# Pro_Trinket_Keyboard_V3_3.net
KiCad netlist of a schematic drawn in EAGLE
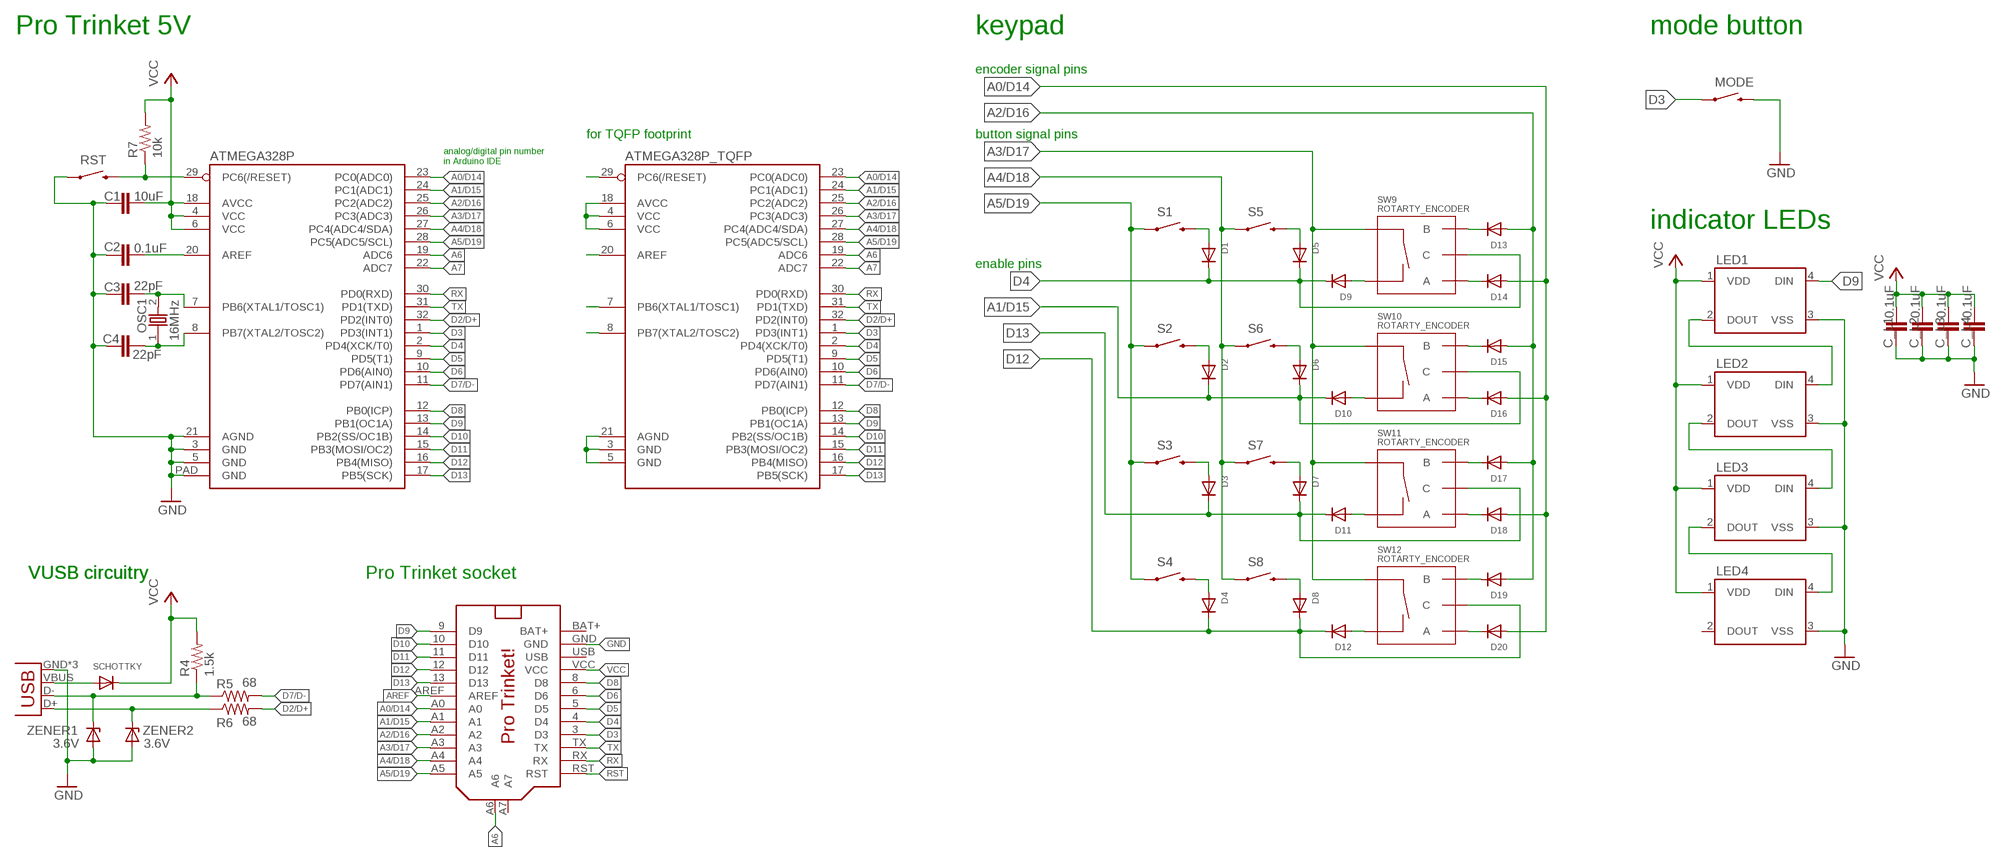
[diagram p0: schematic, sheet 1]

(export (version "E")
  (design (tool "Eeschema 10.0.6"))
  (components
    (comp (ref "ATMEGA328P")
      (value "ATMEGA328P_MLFMLF32")
      (footprint "eagle-import:MLF32-PAD")
      (libsource (lib "eagle-import") (part "ATMEGA328P_MLFMLF32"))
    )
    (comp (ref "ATMEGA328P_TQFP")
      (value "ATMEGA328P_TQFP")
      (footprint "eagle-import:TQFP32-08")
      (libsource (lib "eagle-import") (part "ATMEGA328P_TQFP"))
    )
    (comp (ref "C1")
      (value "10uF")
      (footprint "eagle-import:0603-CAP")
      (libsource (lib "eagle-import") (part "10UF-6.3V-20%(0603)"))
    )
    (comp (ref "C2")
      (value "0.1uF")
      (footprint "eagle-import:0603-CAP")
      (libsource (lib "eagle-import") (part "22PF-50V-5%(0603)"))
    )
    (comp (ref "C3")
      (value "22pF")
      (footprint "eagle-import:0603-CAP")
      (libsource (lib "eagle-import") (part "22PF-50V-5%(0603)"))
    )
    (comp (ref "C4")
      (value "22pF")
      (footprint "eagle-import:0603-CAP")
      (libsource (lib "eagle-import") (part "22PF-50V-5%(0603)"))
    )
    (comp (ref "C_L1")
      (value "0.1uF")
      (footprint "eagle-import:0603-CAP")
      (libsource (lib "eagle-import") (part "22PF-50V-5%(0603)"))
    )
    (comp (ref "C_L2")
      (value "0.1uF")
      (footprint "eagle-import:0603-CAP")
      (libsource (lib "eagle-import") (part "22PF-50V-5%(0603)"))
    )
    (comp (ref "C_L3")
      (value "0.1uF")
      (footprint "eagle-import:0603-CAP")
      (libsource (lib "eagle-import") (part "22PF-50V-5%(0603)"))
    )
    (comp (ref "C_L4")
      (value "0.1uF")
      (footprint "eagle-import:0603-CAP")
      (libsource (lib "eagle-import") (part "22PF-50V-5%(0603)"))
    )
    (comp (ref "D1")
      (value "DIODESOD-123")
      (footprint "eagle-import:SOD-123")
      (libsource (lib "eagle-import") (part "DIODESOD-123"))
    )
    (comp (ref "D2")
      (value "DIODESOD-123")
      (footprint "eagle-import:SOD-123")
      (libsource (lib "eagle-import") (part "DIODESOD-123"))
    )
    (comp (ref "D3")
      (value "DIODESOD-123")
      (footprint "eagle-import:SOD-123")
      (libsource (lib "eagle-import") (part "DIODESOD-123"))
    )
    (comp (ref "D4")
      (value "DIODESOD-123")
      (footprint "eagle-import:SOD-123")
      (libsource (lib "eagle-import") (part "DIODESOD-123"))
    )
    (comp (ref "D5")
      (value "DIODESOD-123")
      (footprint "eagle-import:SOD-123")
      (libsource (lib "eagle-import") (part "DIODESOD-123"))
    )
    (comp (ref "D6")
      (value "DIODESOD-123")
      (footprint "eagle-import:SOD-123")
      (libsource (lib "eagle-import") (part "DIODESOD-123"))
    )
    (comp (ref "D7")
      (value "DIODESOD-123")
      (footprint "eagle-import:SOD-123")
      (libsource (lib "eagle-import") (part "DIODESOD-123"))
    )
    (comp (ref "D8")
      (value "DIODESOD-123")
      (footprint "eagle-import:SOD-123")
      (libsource (lib "eagle-import") (part "DIODESOD-123"))
    )
    (comp (ref "D9")
      (value "DIODESOD-123")
      (footprint "eagle-import:SOD-123")
      (libsource (lib "eagle-import") (part "DIODESOD-123"))
    )
    (comp (ref "D10")
      (value "DIODESOD-123")
      (footprint "eagle-import:SOD-123")
      (libsource (lib "eagle-import") (part "DIODESOD-123"))
    )
    (comp (ref "D11")
      (value "DIODESOD-123")
      (footprint "eagle-import:SOD-123")
      (libsource (lib "eagle-import") (part "DIODESOD-123"))
    )
    (comp (ref "D12")
      (value "DIODESOD-123")
      (footprint "eagle-import:SOD-123")
      (libsource (lib "eagle-import") (part "DIODESOD-123"))
    )
    (comp (ref "D13")
      (value "DIODESOD-123")
      (footprint "eagle-import:SOD-123")
      (libsource (lib "eagle-import") (part "DIODESOD-123"))
    )
    (comp (ref "D14")
      (value "DIODESOD-123")
      (footprint "eagle-import:SOD-123")
      (libsource (lib "eagle-import") (part "DIODESOD-123"))
    )
    (comp (ref "D15")
      (value "DIODESOD-123")
      (footprint "eagle-import:SOD-123")
      (libsource (lib "eagle-import") (part "DIODESOD-123"))
    )
    (comp (ref "D16")
      (value "DIODESOD-123")
      (footprint "eagle-import:SOD-123")
      (libsource (lib "eagle-import") (part "DIODESOD-123"))
    )
    (comp (ref "D17")
      (value "DIODESOD-123")
      (footprint "eagle-import:SOD-123")
      (libsource (lib "eagle-import") (part "DIODESOD-123"))
    )
    (comp (ref "D18")
      (value "DIODESOD-123")
      (footprint "eagle-import:SOD-123")
      (libsource (lib "eagle-import") (part "DIODESOD-123"))
    )
    (comp (ref "D19")
      (value "DIODESOD-123")
      (footprint "eagle-import:SOD-123")
      (libsource (lib "eagle-import") (part "DIODESOD-123"))
    )
    (comp (ref "D20")
      (value "DIODESOD-123")
      (footprint "eagle-import:SOD-123")
      (libsource (lib "eagle-import") (part "DIODESOD-123"))
    )
    (comp (ref "JP1")
      (value "USB-MICROB")
      (footprint "eagle-import:USB-MICROB")
      (libsource (lib "eagle-import") (part "USB-MICROB"))
    )
    (comp (ref "LED1")
      (value "WS2812B")
      (footprint "eagle-import:WS2812B")
      (libsource (lib "eagle-import") (part "WS2812B"))
    )
    (comp (ref "LED2")
      (value "WS2812B")
      (footprint "eagle-import:WS2812B")
      (libsource (lib "eagle-import") (part "WS2812B"))
    )
    (comp (ref "LED3")
      (value "WS2812B")
      (footprint "eagle-import:WS2812B")
      (libsource (lib "eagle-import") (part "WS2812B"))
    )
    (comp (ref "LED4")
      (value "WS2812B")
      (footprint "eagle-import:WS2812B")
      (libsource (lib "eagle-import") (part "WS2812B"))
    )
    (comp (ref "MODE")
      (value "SWITCH-MOMENTARY-2SIDE_EZ")
      (footprint "eagle-import:TACTILE-PTH-SIDEEZ")
      (libsource (lib "eagle-import") (part "SWITCH-MOMENTARY-2SIDE_EZ"))
    )
    (comp (ref "OSC1")
      (value "16MHz")
      (footprint "eagle-import:HC-49U")
      (libsource (lib "eagle-import") (part "OSC-XTAL-HC-49U-SMD"))
    )
    (comp (ref "R4")
      (value "1.5k")
      (footprint "eagle-import:0805")
      (libsource (lib "eagle-import") (part "RESISTOR0805-RES"))
    )
    (comp (ref "R5")
      (value "68")
      (footprint "eagle-import:0805")
      (libsource (lib "eagle-import") (part "RESISTOR0805-RES"))
    )
    (comp (ref "R6")
      (value "68")
      (footprint "eagle-import:0805")
      (libsource (lib "eagle-import") (part "RESISTOR0805-RES"))
    )
    (comp (ref "R7")
      (value "10k")
      (footprint "eagle-import:0805")
      (libsource (lib "eagle-import") (part "RESISTOR0805-RES"))
    )
    (comp (ref "RST")
      (value "SWITCH-MOMENTARY-2SIDE_EZ")
      (footprint "eagle-import:TACTILE-PTH-SIDEEZ")
      (libsource (lib "eagle-import") (part "SWITCH-MOMENTARY-2SIDE_EZ"))
    )
    (comp (ref "S1")
      (value "SWITCH-MOMENTARY-212MM")
      (footprint "eagle-import:TACTILE-PTH-12MM")
      (libsource (lib "eagle-import") (part "SWITCH-MOMENTARY-212MM"))
    )
    (comp (ref "S2")
      (value "SWITCH-MOMENTARY-212MM")
      (footprint "eagle-import:TACTILE-PTH-12MM")
      (libsource (lib "eagle-import") (part "SWITCH-MOMENTARY-212MM"))
    )
    (comp (ref "S3")
      (value "SWITCH-MOMENTARY-212MM")
      (footprint "eagle-import:TACTILE-PTH-12MM")
      (libsource (lib "eagle-import") (part "SWITCH-MOMENTARY-212MM"))
    )
    (comp (ref "S4")
      (value "SWITCH-MOMENTARY-212MM")
      (footprint "eagle-import:TACTILE-PTH-12MM")
      (libsource (lib "eagle-import") (part "SWITCH-MOMENTARY-212MM"))
    )
    (comp (ref "S5")
      (value "SWITCH-MOMENTARY-212MM")
      (footprint "eagle-import:TACTILE-PTH-12MM")
      (libsource (lib "eagle-import") (part "SWITCH-MOMENTARY-212MM"))
    )
    (comp (ref "S6")
      (value "SWITCH-MOMENTARY-212MM")
      (footprint "eagle-import:TACTILE-PTH-12MM")
      (libsource (lib "eagle-import") (part "SWITCH-MOMENTARY-212MM"))
    )
    (comp (ref "S7")
      (value "SWITCH-MOMENTARY-212MM")
      (footprint "eagle-import:TACTILE-PTH-12MM")
      (libsource (lib "eagle-import") (part "SWITCH-MOMENTARY-212MM"))
    )
    (comp (ref "S8")
      (value "SWITCH-MOMENTARY-212MM")
      (footprint "eagle-import:TACTILE-PTH-12MM")
      (libsource (lib "eagle-import") (part "SWITCH-MOMENTARY-212MM"))
    )
    (comp (ref "SCHOTTKY")
      (value "DIODESMA")
      (footprint "eagle-import:SMADIODE")
      (libsource (lib "eagle-import") (part "DIODESMA"))
    )
    (comp (ref "SW9")
      (value "ROTARTY_ENCODER")
      (footprint "eagle-import:ROTARY_ENC_PLAIN")
      (libsource (lib "eagle-import") (part "ROTARTY_ENCODER"))
    )
    (comp (ref "SW10")
      (value "ROTARTY_ENCODER")
      (footprint "eagle-import:ROTARY_ENC_PLAIN")
      (libsource (lib "eagle-import") (part "ROTARTY_ENCODER"))
    )
    (comp (ref "SW11")
      (value "ROTARTY_ENCODER")
      (footprint "eagle-import:ROTARY_ENC_PLAIN")
      (libsource (lib "eagle-import") (part "ROTARTY_ENCODER"))
    )
    (comp (ref "SW12")
      (value "ROTARTY_ENCODER")
      (footprint "eagle-import:ROTARY_ENC_PLAIN")
      (libsource (lib "eagle-import") (part "ROTARTY_ENCODER"))
    )
    (comp (ref "U$2")
      (value "PRO_TRINKET")
      (footprint "eagle-import:PROTRINKET")
      (libsource (lib "eagle-import") (part "PRO_TRINKET"))
    )
    (comp (ref "ZENER1")
      (value "3.6V")
      (footprint "eagle-import:SOD80C")
      (libsource (lib "eagle-import") (part "ZENER-DIODESOD80C"))
    )
    (comp (ref "ZENER2")
      (value "3.6V")
      (footprint "eagle-import:SOD80C")
      (libsource (lib "eagle-import") (part "ZENER-DIODESOD80C"))
    )
  )
  (nets
    (net (code "1") (name "/BAT+") (class "Default")
      (node (ref "U$2") (pin "BAT+") (pinfunction "BAT+_BAT+") (pintype "power_in"))
    )
    (net (code "2") (name "/USB") (class "Default")
      (node (ref "U$2") (pin "USB") (pinfunction "USB_USB") (pintype "power_in"))
    )
    (net (code "3") (name "/XTAL1") (class "Default")
      (node (ref "ATMEGA328P") (pin "7") (pinfunction "PB6(XTAL1/TOSC1)_7") (pintype "bidirectional"))
      (node (ref "ATMEGA328P_TQFP") (pin "7") (pinfunction "PB6(XTAL1/TOSC1)_7") (pintype "bidirectional"))
      (node (ref "C3") (pin "2") (pinfunction "2_2") (pintype "passive"))
      (node (ref "OSC1") (pin "2") (pinfunction "2_2") (pintype "passive"))
    )
    (net (code "4") (name "/XTAL2") (class "Default")
      (node (ref "ATMEGA328P") (pin "8") (pinfunction "PB7(XTAL2/TOSC2)_8") (pintype "bidirectional"))
      (node (ref "ATMEGA328P_TQFP") (pin "8") (pinfunction "PB7(XTAL2/TOSC2)_8") (pintype "bidirectional"))
      (node (ref "C4") (pin "1") (pinfunction "1_1") (pintype "passive"))
      (node (ref "OSC1") (pin "1") (pinfunction "1_1") (pintype "passive"))
    )
    (net (code "5") (name "A0{slash}D14") (class "Default")
      (node (ref "ATMEGA328P") (pin "23") (pinfunction "PC0(ADC0)_23") (pintype "bidirectional"))
      (node (ref "ATMEGA328P_TQFP") (pin "23") (pinfunction "PC0(ADC0)_23") (pintype "bidirectional"))
      (node (ref "D14") (pin "A") (pinfunction "A_A") (pintype "passive"))
      (node (ref "D16") (pin "A") (pinfunction "A_A") (pintype "passive"))
      (node (ref "D18") (pin "A") (pinfunction "A_A") (pintype "passive"))
      (node (ref "D20") (pin "A") (pinfunction "A_A") (pintype "passive"))
      (node (ref "U$2") (pin "A0") (pinfunction "A0_A0") (pintype "bidirectional"))
    )
    (net (code "6") (name "A1{slash}D15") (class "Default")
      (node (ref "ATMEGA328P") (pin "24") (pinfunction "PC1(ADC1)_24") (pintype "bidirectional"))
      (node (ref "ATMEGA328P_TQFP") (pin "24") (pinfunction "PC1(ADC1)_24") (pintype "bidirectional"))
      (node (ref "D10") (pin "C") (pinfunction "C_C") (pintype "passive"))
      (node (ref "D2") (pin "C") (pinfunction "C_C") (pintype "passive"))
      (node (ref "D6") (pin "C") (pinfunction "C_C") (pintype "passive"))
      (node (ref "SW10") (pin "C") (pinfunction "C_C") (pintype "bidirectional"))
      (node (ref "U$2") (pin "A1") (pinfunction "A1_A1") (pintype "bidirectional"))
    )
    (net (code "7") (name "A2{slash}D16") (class "Default")
      (node (ref "ATMEGA328P") (pin "25") (pinfunction "PC2(ADC2)_25") (pintype "bidirectional"))
      (node (ref "ATMEGA328P_TQFP") (pin "25") (pinfunction "PC2(ADC2)_25") (pintype "bidirectional"))
      (node (ref "D13") (pin "A") (pinfunction "A_A") (pintype "passive"))
      (node (ref "D15") (pin "A") (pinfunction "A_A") (pintype "passive"))
      (node (ref "D17") (pin "A") (pinfunction "A_A") (pintype "passive"))
      (node (ref "D19") (pin "A") (pinfunction "A_A") (pintype "passive"))
      (node (ref "U$2") (pin "A2") (pinfunction "A2_A2") (pintype "bidirectional"))
    )
    (net (code "8") (name "A3{slash}D17") (class "Default")
      (node (ref "ATMEGA328P") (pin "26") (pinfunction "PC3(ADC3)_26") (pintype "bidirectional"))
      (node (ref "ATMEGA328P_TQFP") (pin "26") (pinfunction "PC3(ADC3)_26") (pintype "bidirectional"))
      (node (ref "SW10") (pin "SW+") (pinfunction "SW+_SW+") (pintype "bidirectional"))
      (node (ref "SW11") (pin "SW+") (pinfunction "SW+_SW+") (pintype "bidirectional"))
      (node (ref "SW12") (pin "SW+") (pinfunction "SW+_SW+") (pintype "bidirectional"))
      (node (ref "SW9") (pin "SW+") (pinfunction "SW+_SW+") (pintype "bidirectional"))
      (node (ref "U$2") (pin "A3") (pinfunction "A3_A3") (pintype "bidirectional"))
    )
    (net (code "9") (name "A4{slash}D18") (class "Default")
      (node (ref "ATMEGA328P") (pin "27") (pinfunction "PC4(ADC4/SDA)_27") (pintype "bidirectional"))
      (node (ref "ATMEGA328P_TQFP") (pin "27") (pinfunction "PC4(ADC4/SDA)_27") (pintype "bidirectional"))
      (node (ref "S5") (pin "1") (pinfunction "1_1") (pintype "passive"))
      (node (ref "S5") (pin "2") (pinfunction "1_2") (pintype "passive"))
      (node (ref "S6") (pin "1") (pinfunction "1_1") (pintype "passive"))
      (node (ref "S6") (pin "2") (pinfunction "1_2") (pintype "passive"))
      (node (ref "S7") (pin "1") (pinfunction "1_1") (pintype "passive"))
      (node (ref "S7") (pin "2") (pinfunction "1_2") (pintype "passive"))
      (node (ref "S8") (pin "1") (pinfunction "1_1") (pintype "passive"))
      (node (ref "S8") (pin "2") (pinfunction "1_2") (pintype "passive"))
      (node (ref "U$2") (pin "A4") (pinfunction "A4_A4") (pintype "bidirectional"))
    )
    (net (code "10") (name "A5{slash}D19") (class "Default")
      (node (ref "ATMEGA328P") (pin "28") (pinfunction "PC5(ADC5/SCL)_28") (pintype "bidirectional"))
      (node (ref "ATMEGA328P_TQFP") (pin "28") (pinfunction "PC5(ADC5/SCL)_28") (pintype "bidirectional"))
      (node (ref "S1") (pin "1") (pinfunction "1_1") (pintype "passive"))
      (node (ref "S1") (pin "2") (pinfunction "1_2") (pintype "passive"))
      (node (ref "S2") (pin "1") (pinfunction "1_1") (pintype "passive"))
      (node (ref "S2") (pin "2") (pinfunction "1_2") (pintype "passive"))
      (node (ref "S3") (pin "1") (pinfunction "1_1") (pintype "passive"))
      (node (ref "S3") (pin "2") (pinfunction "1_2") (pintype "passive"))
      (node (ref "S4") (pin "1") (pinfunction "1_1") (pintype "passive"))
      (node (ref "S4") (pin "2") (pinfunction "1_2") (pintype "passive"))
      (node (ref "U$2") (pin "A5") (pinfunction "A5_A5") (pintype "bidirectional"))
    )
    (net (code "11") (name "A6") (class "Default")
      (node (ref "ATMEGA328P") (pin "19") (pinfunction "ADC6_19") (pintype "bidirectional"))
      (node (ref "ATMEGA328P_TQFP") (pin "19") (pinfunction "ADC6_19") (pintype "bidirectional"))
      (node (ref "U$2") (pin "A6") (pinfunction "A6_A6") (pintype "passive"))
    )
    (net (code "12") (name "A7") (class "Default")
      (node (ref "ATMEGA328P") (pin "22") (pinfunction "ADC7_22") (pintype "bidirectional"))
      (node (ref "ATMEGA328P_TQFP") (pin "22") (pinfunction "ADC7_22") (pintype "bidirectional"))
    )
    (net (code "13") (name "AREF") (class "Default")
      (node (ref "ATMEGA328P") (pin "20") (pinfunction "AREF_20") (pintype "bidirectional"))
      (node (ref "ATMEGA328P_TQFP") (pin "20") (pinfunction "AREF_20") (pintype "bidirectional"))
      (node (ref "C2") (pin "2") (pinfunction "2_2") (pintype "passive"))
      (node (ref "U$2") (pin "AREF") (pinfunction "AREF_AREF") (pintype "passive"))
    )
    (net (code "14") (name "D2{slash}D+") (class "Default")
      (node (ref "ATMEGA328P") (pin "32") (pinfunction "PD2(INT0)_32") (pintype "bidirectional"))
      (node (ref "ATMEGA328P_TQFP") (pin "32") (pinfunction "PD2(INT0)_32") (pintype "bidirectional"))
      (node (ref "R6") (pin "2") (pinfunction "2_2") (pintype "passive"))
    )
    (net (code "15") (name "D3") (class "Default")
      (node (ref "ATMEGA328P") (pin "1") (pinfunction "PD3(INT1)_1") (pintype "bidirectional"))
      (node (ref "ATMEGA328P_TQFP") (pin "1") (pinfunction "PD3(INT1)_1") (pintype "bidirectional"))
      (node (ref "MODE") (pin "1") (pinfunction "1_1") (pintype "passive"))
      (node (ref "U$2") (pin "3") (pinfunction "D3_3") (pintype "bidirectional"))
    )
    (net (code "16") (name "D4") (class "Default")
      (node (ref "ATMEGA328P") (pin "2") (pinfunction "PD4(XCK/T0)_2") (pintype "bidirectional"))
      (node (ref "ATMEGA328P_TQFP") (pin "2") (pinfunction "PD4(XCK/T0)_2") (pintype "bidirectional"))
      (node (ref "D1") (pin "C") (pinfunction "C_C") (pintype "passive"))
      (node (ref "D5") (pin "C") (pinfunction "C_C") (pintype "passive"))
      (node (ref "D9") (pin "C") (pinfunction "C_C") (pintype "passive"))
      (node (ref "SW9") (pin "C") (pinfunction "C_C") (pintype "bidirectional"))
      (node (ref "U$2") (pin "4") (pinfunction "D4_4") (pintype "bidirectional"))
    )
    (net (code "17") (name "D5") (class "Default")
      (node (ref "ATMEGA328P") (pin "9") (pinfunction "PD5(T1)_9") (pintype "bidirectional"))
      (node (ref "ATMEGA328P_TQFP") (pin "9") (pinfunction "PD5(T1)_9") (pintype "bidirectional"))
      (node (ref "U$2") (pin "5") (pinfunction "D5_5") (pintype "bidirectional"))
    )
    (net (code "18") (name "D6") (class "Default")
      (node (ref "ATMEGA328P") (pin "10") (pinfunction "PD6(AIN0)_10") (pintype "bidirectional"))
      (node (ref "ATMEGA328P_TQFP") (pin "10") (pinfunction "PD6(AIN0)_10") (pintype "bidirectional"))
      (node (ref "U$2") (pin "6") (pinfunction "D6_6") (pintype "bidirectional"))
    )
    (net (code "19") (name "D7{slash}D-") (class "Default")
      (node (ref "ATMEGA328P") (pin "11") (pinfunction "PD7(AIN1)_11") (pintype "bidirectional"))
      (node (ref "ATMEGA328P_TQFP") (pin "11") (pinfunction "PD7(AIN1)_11") (pintype "bidirectional"))
      (node (ref "R5") (pin "2") (pinfunction "2_2") (pintype "passive"))
    )
    (net (code "20") (name "D8") (class "Default")
      (node (ref "ATMEGA328P") (pin "12") (pinfunction "PB0(ICP)_12") (pintype "bidirectional"))
      (node (ref "ATMEGA328P_TQFP") (pin "12") (pinfunction "PB0(ICP)_12") (pintype "bidirectional"))
      (node (ref "U$2") (pin "8") (pinfunction "D8_8") (pintype "bidirectional"))
    )
    (net (code "21") (name "D9") (class "Default")
      (node (ref "ATMEGA328P") (pin "13") (pinfunction "PB1(OC1A)_13") (pintype "bidirectional"))
      (node (ref "ATMEGA328P_TQFP") (pin "13") (pinfunction "PB1(OC1A)_13") (pintype "bidirectional"))
      (node (ref "LED1") (pin "4") (pinfunction "DIN_4") (pintype "input"))
      (node (ref "U$2") (pin "9") (pinfunction "D9_9") (pintype "bidirectional"))
    )
    (net (code "22") (name "D10") (class "Default")
      (node (ref "ATMEGA328P") (pin "14") (pinfunction "PB2(SS/OC1B)_14") (pintype "bidirectional"))
      (node (ref "ATMEGA328P_TQFP") (pin "14") (pinfunction "PB2(SS/OC1B)_14") (pintype "bidirectional"))
      (node (ref "U$2") (pin "10") (pinfunction "D10_10") (pintype "bidirectional"))
    )
    (net (code "23") (name "D11") (class "Default")
      (node (ref "ATMEGA328P") (pin "15") (pinfunction "PB3(MOSI/OC2)_15") (pintype "bidirectional"))
      (node (ref "ATMEGA328P_TQFP") (pin "15") (pinfunction "PB3(MOSI/OC2)_15") (pintype "bidirectional"))
      (node (ref "U$2") (pin "11") (pinfunction "D11_11") (pintype "bidirectional"))
    )
    (net (code "24") (name "D12") (class "Default")
      (node (ref "ATMEGA328P") (pin "16") (pinfunction "PB4(MISO)_16") (pintype "bidirectional"))
      (node (ref "ATMEGA328P_TQFP") (pin "16") (pinfunction "PB4(MISO)_16") (pintype "bidirectional"))
      (node (ref "D12") (pin "C") (pinfunction "C_C") (pintype "passive"))
      (node (ref "D4") (pin "C") (pinfunction "C_C") (pintype "passive"))
      (node (ref "D8") (pin "C") (pinfunction "C_C") (pintype "passive"))
      (node (ref "SW12") (pin "C") (pinfunction "C_C") (pintype "bidirectional"))
      (node (ref "U$2") (pin "12") (pinfunction "D12_12") (pintype "bidirectional"))
    )
    (net (code "25") (name "D13") (class "Default")
      (node (ref "ATMEGA328P") (pin "17") (pinfunction "PB5(SCK)_17") (pintype "bidirectional"))
      (node (ref "ATMEGA328P_TQFP") (pin "17") (pinfunction "PB5(SCK)_17") (pintype "bidirectional"))
      (node (ref "D11") (pin "C") (pinfunction "C_C") (pintype "passive"))
      (node (ref "D3") (pin "C") (pinfunction "C_C") (pintype "passive"))
      (node (ref "D7") (pin "C") (pinfunction "C_C") (pintype "passive"))
      (node (ref "SW11") (pin "C") (pinfunction "C_C") (pintype "bidirectional"))
      (node (ref "U$2") (pin "13") (pinfunction "D13_13") (pintype "bidirectional"))
    )
    (net (code "26") (name "GND") (class "Default")
      (node (ref "ATMEGA328P") (pin "21") (pinfunction "AGND_21") (pintype "bidirectional"))
      (node (ref "ATMEGA328P") (pin "3") (pinfunction "GND_3") (pintype "bidirectional"))
      (node (ref "ATMEGA328P") (pin "5") (pinfunction "GND_5") (pintype "bidirectional"))
      (node (ref "ATMEGA328P") (pin "PAD") (pinfunction "GND_PAD") (pintype "bidirectional"))
      (node (ref "ATMEGA328P_TQFP") (pin "21") (pinfunction "AGND_21") (pintype "bidirectional"))
      (node (ref "ATMEGA328P_TQFP") (pin "3") (pinfunction "GND_3") (pintype "bidirectional"))
      (node (ref "ATMEGA328P_TQFP") (pin "5") (pinfunction "GND_5") (pintype "bidirectional"))
      (node (ref "C1") (pin "1") (pinfunction "1_1") (pintype "passive"))
      (node (ref "C2") (pin "1") (pinfunction "1_1") (pintype "passive"))
      (node (ref "C3") (pin "1") (pinfunction "1_1") (pintype "passive"))
      (node (ref "C4") (pin "2") (pinfunction "2_2") (pintype "passive"))
      (node (ref "C_L1") (pin "1") (pinfunction "1_1") (pintype "passive"))
      (node (ref "C_L2") (pin "1") (pinfunction "1_1") (pintype "passive"))
      (node (ref "C_L3") (pin "1") (pinfunction "1_1") (pintype "passive"))
      (node (ref "C_L4") (pin "1") (pinfunction "1_1") (pintype "passive"))
      (node (ref "JP1") (pin "GND") (pinfunction "GND_GND") (pintype "bidirectional"))
      (node (ref "JP1") (pin "MT1") (pinfunction "GND_MT1") (pintype "bidirectional"))
      (node (ref "JP1") (pin "MT2") (pinfunction "GND_MT2") (pintype "bidirectional"))
      (node (ref "LED1") (pin "3") (pinfunction "VSS_3") (pintype "power_in"))
      (node (ref "LED2") (pin "3") (pinfunction "VSS_3") (pintype "power_in"))
      (node (ref "LED3") (pin "3") (pinfunction "VSS_3") (pintype "power_in"))
      (node (ref "LED4") (pin "3") (pinfunction "VSS_3") (pintype "power_in"))
      (node (ref "MODE") (pin "2") (pinfunction "2_2") (pintype "passive"))
      (node (ref "RST") (pin "1") (pinfunction "1_1") (pintype "passive"))
      (node (ref "U$2") (pin "GND") (pinfunction "GND_GND") (pintype "power_in"))
      (node (ref "ZENER1") (pin "A") (pinfunction "A_A") (pintype "passive"))
      (node (ref "ZENER2") (pin "A") (pinfunction "A_A") (pintype "passive"))
    )
    (net (code "27") (name "Net-(D1-PadA)") (class "Default")
      (node (ref "D1") (pin "A") (pinfunction "A_A") (pintype "passive"))
      (node (ref "S1") (pin "3") (pinfunction "2_3") (pintype "passive"))
      (node (ref "S1") (pin "4") (pinfunction "2_4") (pintype "passive"))
    )
    (net (code "28") (name "Net-(D2-PadA)") (class "Default")
      (node (ref "D2") (pin "A") (pinfunction "A_A") (pintype "passive"))
      (node (ref "S2") (pin "3") (pinfunction "2_3") (pintype "passive"))
      (node (ref "S2") (pin "4") (pinfunction "2_4") (pintype "passive"))
    )
    (net (code "29") (name "Net-(D3-PadA)") (class "Default")
      (node (ref "D3") (pin "A") (pinfunction "A_A") (pintype "passive"))
      (node (ref "S3") (pin "3") (pinfunction "2_3") (pintype "passive"))
      (node (ref "S3") (pin "4") (pinfunction "2_4") (pintype "passive"))
    )
    (net (code "30") (name "Net-(D4-PadA)") (class "Default")
      (node (ref "D4") (pin "A") (pinfunction "A_A") (pintype "passive"))
      (node (ref "S4") (pin "3") (pinfunction "2_3") (pintype "passive"))
      (node (ref "S4") (pin "4") (pinfunction "2_4") (pintype "passive"))
    )
    (net (code "31") (name "Net-(D5-PadA)") (class "Default")
      (node (ref "D5") (pin "A") (pinfunction "A_A") (pintype "passive"))
      (node (ref "S5") (pin "3") (pinfunction "2_3") (pintype "passive"))
      (node (ref "S5") (pin "4") (pinfunction "2_4") (pintype "passive"))
    )
    (net (code "32") (name "Net-(D6-PadA)") (class "Default")
      (node (ref "D6") (pin "A") (pinfunction "A_A") (pintype "passive"))
      (node (ref "S6") (pin "3") (pinfunction "2_3") (pintype "passive"))
      (node (ref "S6") (pin "4") (pinfunction "2_4") (pintype "passive"))
    )
    (net (code "33") (name "Net-(D7-PadA)") (class "Default")
      (node (ref "D7") (pin "A") (pinfunction "A_A") (pintype "passive"))
      (node (ref "S7") (pin "3") (pinfunction "2_3") (pintype "passive"))
      (node (ref "S7") (pin "4") (pinfunction "2_4") (pintype "passive"))
    )
    (net (code "34") (name "Net-(D8-PadA)") (class "Default")
      (node (ref "D8") (pin "A") (pinfunction "A_A") (pintype "passive"))
      (node (ref "S8") (pin "3") (pinfunction "2_3") (pintype "passive"))
      (node (ref "S8") (pin "4") (pinfunction "2_4") (pintype "passive"))
    )
    (net (code "35") (name "Net-(D9-PadA)") (class "Default")
      (node (ref "D9") (pin "A") (pinfunction "A_A") (pintype "passive"))
      (node (ref "SW9") (pin "SW-") (pinfunction "SW-_SW-") (pintype "bidirectional"))
    )
    (net (code "36") (name "Net-(D10-PadA)") (class "Default")
      (node (ref "D10") (pin "A") (pinfunction "A_A") (pintype "passive"))
      (node (ref "SW10") (pin "SW-") (pinfunction "SW-_SW-") (pintype "bidirectional"))
    )
    (net (code "37") (name "Net-(D11-PadA)") (class "Default")
      (node (ref "D11") (pin "A") (pinfunction "A_A") (pintype "passive"))
      (node (ref "SW11") (pin "SW-") (pinfunction "SW-_SW-") (pintype "bidirectional"))
    )
    (net (code "38") (name "Net-(D12-PadA)") (class "Default")
      (node (ref "D12") (pin "A") (pinfunction "A_A") (pintype "passive"))
      (node (ref "SW12") (pin "SW-") (pinfunction "SW-_SW-") (pintype "bidirectional"))
    )
    (net (code "39") (name "Net-(D13-PadC)") (class "Default")
      (node (ref "D13") (pin "C") (pinfunction "C_C") (pintype "passive"))
      (node (ref "SW9") (pin "B") (pinfunction "B_B") (pintype "bidirectional"))
    )
    (net (code "40") (name "Net-(D14-PadC)") (class "Default")
      (node (ref "D14") (pin "C") (pinfunction "C_C") (pintype "passive"))
      (node (ref "SW9") (pin "A") (pinfunction "A_A") (pintype "bidirectional"))
    )
    (net (code "41") (name "Net-(D15-PadC)") (class "Default")
      (node (ref "D15") (pin "C") (pinfunction "C_C") (pintype "passive"))
      (node (ref "SW10") (pin "B") (pinfunction "B_B") (pintype "bidirectional"))
    )
    (net (code "42") (name "Net-(D16-PadC)") (class "Default")
      (node (ref "D16") (pin "C") (pinfunction "C_C") (pintype "passive"))
      (node (ref "SW10") (pin "A") (pinfunction "A_A") (pintype "bidirectional"))
    )
    (net (code "43") (name "Net-(D17-PadC)") (class "Default")
      (node (ref "D17") (pin "C") (pinfunction "C_C") (pintype "passive"))
      (node (ref "SW11") (pin "B") (pinfunction "B_B") (pintype "bidirectional"))
    )
    (net (code "44") (name "Net-(D18-PadC)") (class "Default")
      (node (ref "D18") (pin "C") (pinfunction "C_C") (pintype "passive"))
      (node (ref "SW11") (pin "A") (pinfunction "A_A") (pintype "bidirectional"))
    )
    (net (code "45") (name "Net-(D19-PadC)") (class "Default")
      (node (ref "D19") (pin "C") (pinfunction "C_C") (pintype "passive"))
      (node (ref "SW12") (pin "B") (pinfunction "B_B") (pintype "bidirectional"))
    )
    (net (code "46") (name "Net-(D20-PadC)") (class "Default")
      (node (ref "D20") (pin "C") (pinfunction "C_C") (pintype "passive"))
      (node (ref "SW12") (pin "A") (pinfunction "A_A") (pintype "bidirectional"))
    )
    (net (code "47") (name "Net-(JP1-PadD+)") (class "Default")
      (node (ref "JP1") (pin "D+") (pinfunction "D+_D+") (pintype "bidirectional"))
      (node (ref "R6") (pin "1") (pinfunction "1_1") (pintype "passive"))
      (node (ref "ZENER2") (pin "C") (pinfunction "C_C") (pintype "passive"))
    )
    (net (code "48") (name "Net-(JP1-PadD-)") (class "Default")
      (node (ref "JP1") (pin "D-") (pinfunction "D-_D-") (pintype "bidirectional"))
      (node (ref "R4") (pin "1") (pinfunction "1_1") (pintype "passive"))
      (node (ref "R5") (pin "1") (pinfunction "1_1") (pintype "passive"))
      (node (ref "ZENER1") (pin "C") (pinfunction "C_C") (pintype "passive"))
    )
    (net (code "49") (name "Net-(JP1-PadVBUS)") (class "Default")
      (node (ref "JP1") (pin "VBUS") (pinfunction "VBUS_VBUS") (pintype "bidirectional"))
      (node (ref "SCHOTTKY") (pin "A") (pinfunction "A_A") (pintype "passive"))
    )
    (net (code "50") (name "Net-(LED1-DOUT)") (class "Default")
      (node (ref "LED1") (pin "2") (pinfunction "DOUT_2") (pintype "output"))
      (node (ref "LED2") (pin "4") (pinfunction "DIN_4") (pintype "input"))
    )
    (net (code "51") (name "Net-(LED2-DOUT)") (class "Default")
      (node (ref "LED2") (pin "2") (pinfunction "DOUT_2") (pintype "output"))
      (node (ref "LED3") (pin "4") (pinfunction "DIN_4") (pintype "input"))
    )
    (net (code "52") (name "Net-(LED3-DOUT)") (class "Default")
      (node (ref "LED3") (pin "2") (pinfunction "DOUT_2") (pintype "output"))
      (node (ref "LED4") (pin "4") (pinfunction "DIN_4") (pintype "input"))
    )
    (net (code "53") (name "RST") (class "Default")
      (node (ref "ATMEGA328P") (pin "29") (pinfunction "PC6(/RESET)_29") (pintype "bidirectional"))
      (node (ref "ATMEGA328P_TQFP") (pin "29") (pinfunction "PC6(/RESET)_29") (pintype "bidirectional"))
      (node (ref "R7") (pin "1") (pinfunction "1_1") (pintype "passive"))
      (node (ref "RST") (pin "2") (pinfunction "2_2") (pintype "passive"))
      (node (ref "U$2") (pin "RST") (pinfunction "RST_RST") (pintype "passive"))
    )
    (net (code "54") (name "RX") (class "Default")
      (node (ref "ATMEGA328P") (pin "30") (pinfunction "PD0(RXD)_30") (pintype "bidirectional"))
      (node (ref "ATMEGA328P_TQFP") (pin "30") (pinfunction "PD0(RXD)_30") (pintype "bidirectional"))
      (node (ref "U$2") (pin "RX") (pinfunction "RX_RX") (pintype "bidirectional"))
    )
    (net (code "55") (name "TX") (class "Default")
      (node (ref "ATMEGA328P") (pin "31") (pinfunction "PD1(TXD)_31") (pintype "bidirectional"))
      (node (ref "ATMEGA328P_TQFP") (pin "31") (pinfunction "PD1(TXD)_31") (pintype "bidirectional"))
      (node (ref "U$2") (pin "TX") (pinfunction "TX_TX") (pintype "bidirectional"))
    )
    (net (code "56") (name "VCC") (class "Default")
      (node (ref "ATMEGA328P") (pin "18") (pinfunction "AVCC_18") (pintype "bidirectional"))
      (node (ref "ATMEGA328P") (pin "4") (pinfunction "VCC_4") (pintype "bidirectional"))
      (node (ref "ATMEGA328P") (pin "6") (pinfunction "VCC_6") (pintype "bidirectional"))
      (node (ref "ATMEGA328P_TQFP") (pin "18") (pinfunction "AVCC_18") (pintype "bidirectional"))
      (node (ref "ATMEGA328P_TQFP") (pin "4") (pinfunction "VCC_4") (pintype "bidirectional"))
      (node (ref "ATMEGA328P_TQFP") (pin "6") (pinfunction "VCC_6") (pintype "bidirectional"))
      (node (ref "C1") (pin "2") (pinfunction "2_2") (pintype "passive"))
      (node (ref "C_L1") (pin "2") (pinfunction "2_2") (pintype "passive"))
      (node (ref "C_L2") (pin "2") (pinfunction "2_2") (pintype "passive"))
      (node (ref "C_L3") (pin "2") (pinfunction "2_2") (pintype "passive"))
      (node (ref "C_L4") (pin "2") (pinfunction "2_2") (pintype "passive"))
      (node (ref "LED1") (pin "1") (pinfunction "VDD_1") (pintype "power_in"))
      (node (ref "LED2") (pin "1") (pinfunction "VDD_1") (pintype "power_in"))
      (node (ref "LED3") (pin "1") (pinfunction "VDD_1") (pintype "power_in"))
      (node (ref "LED4") (pin "1") (pinfunction "VDD_1") (pintype "power_in"))
      (node (ref "R4") (pin "2") (pinfunction "2_2") (pintype "passive"))
      (node (ref "R7") (pin "2") (pinfunction "2_2") (pintype "passive"))
      (node (ref "SCHOTTKY") (pin "C") (pinfunction "C_C") (pintype "passive"))
      (node (ref "U$2") (pin "VCC") (pinfunction "VCC_VCC") (pintype "power_in"))
    )
    (net (code "57") (name "unconnected-(LED4-DOUT-Pad2)") (class "Default")
      (node (ref "LED4") (pin "2") (pinfunction "DOUT_2") (pintype "output"))
    )
    (net (code "58") (name "unconnected-(U$2-PadA7)") (class "Default")
      (node (ref "U$2") (pin "A7") (pinfunction "A7_A7") (pintype "passive"))
    )
  )
)
